# ESC.net
KiCad netlist of a schematic drawn in EAGLE
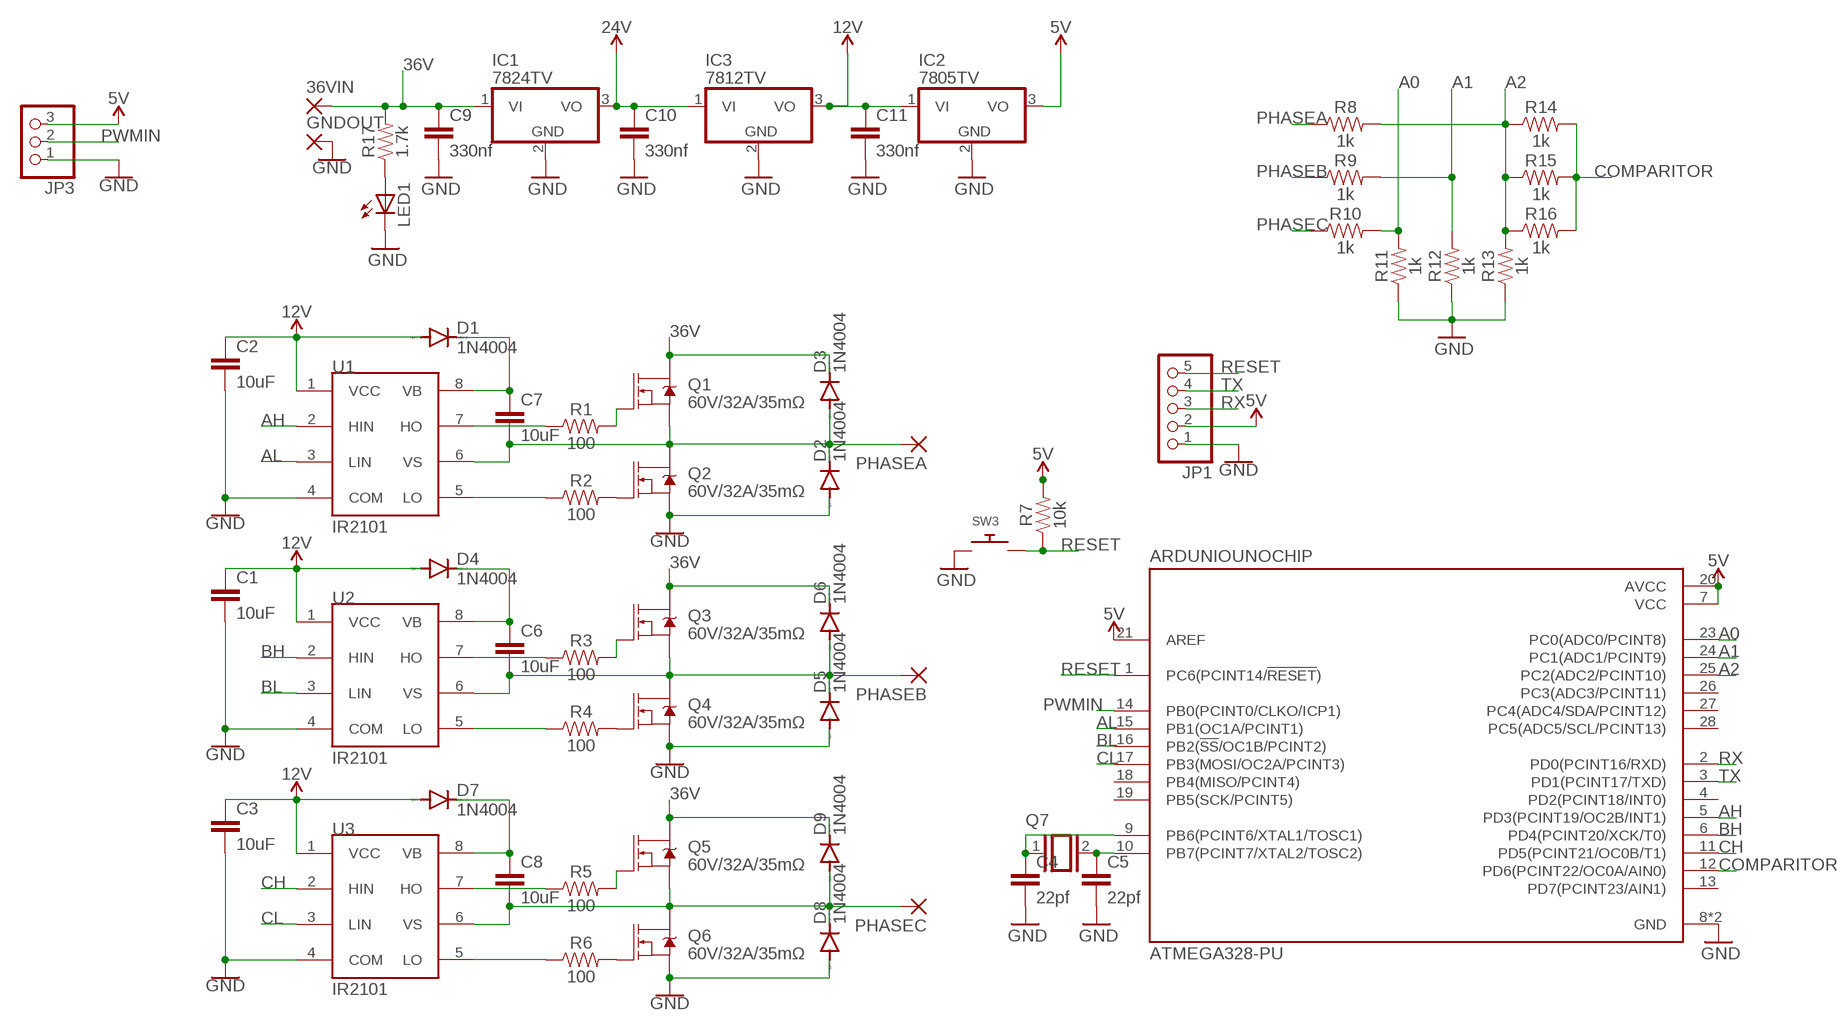
[diagram p0: schematic, sheet 1]

(export (version "E")
  (design (tool "Eeschema 10.0.6"))
  (components
    (comp (ref "36VIN")
      (value "2,15/1,0")
      (footprint "eagle-import:2,15_1,0")
      (libsource (lib "eagle-import") (part "2,15/1,0"))
    )
    (comp (ref "ARDUNIOUNOCHIP")
      (value "ATMEGA328-PU")
      (footprint "eagle-import:DIP787W46P254L3467H508Q28")
      (fields (field (name "MF") "Microchip Technology"))
      (libsource (lib "eagle-import") (part "ATMEGA328-PU"))
    )
    (comp (ref "C1")
      (value "10uF")
      (footprint "eagle-import:CAP-PTH-10MM")
      (libsource (lib "eagle-import") (part "10NF-PTH-10MM-10000V-1-%"))
    )
    (comp (ref "C2")
      (value "10uF")
      (footprint "eagle-import:CAP-PTH-10MM")
      (libsource (lib "eagle-import") (part "10NF-PTH-10MM-10000V-1-%"))
    )
    (comp (ref "C3")
      (value "10uF")
      (footprint "eagle-import:CAP-PTH-10MM")
      (libsource (lib "eagle-import") (part "10NF-PTH-10MM-10000V-1-%"))
    )
    (comp (ref "C4")
      (value "22pf")
      (footprint "eagle-import:CAP-PTH-10MM")
      (libsource (lib "eagle-import") (part "10NF-PTH-10MM-10000V-1-%"))
    )
    (comp (ref "C5")
      (value "22pf")
      (footprint "eagle-import:CAP-PTH-10MM")
      (libsource (lib "eagle-import") (part "10NF-PTH-10MM-10000V-1-%"))
    )
    (comp (ref "C6")
      (value "10uF")
      (footprint "eagle-import:CAP-PTH-10MM")
      (libsource (lib "eagle-import") (part "10NF-PTH-10MM-10000V-1-%"))
    )
    (comp (ref "C7")
      (value "10uF")
      (footprint "eagle-import:CAP-PTH-10MM")
      (libsource (lib "eagle-import") (part "10NF-PTH-10MM-10000V-1-%"))
    )
    (comp (ref "C8")
      (value "10uF")
      (footprint "eagle-import:CAP-PTH-10MM")
      (libsource (lib "eagle-import") (part "10NF-PTH-10MM-10000V-1-%"))
    )
    (comp (ref "C9")
      (value "330nf")
      (footprint "eagle-import:CAP-PTH-10MM")
      (libsource (lib "eagle-import") (part "10NF-PTH-10MM-10000V-1-%"))
    )
    (comp (ref "C10")
      (value "330nf")
      (footprint "eagle-import:CAP-PTH-10MM")
      (libsource (lib "eagle-import") (part "10NF-PTH-10MM-10000V-1-%"))
    )
    (comp (ref "C11")
      (value "330nf")
      (footprint "eagle-import:CAP-PTH-10MM")
      (libsource (lib "eagle-import") (part "10NF-PTH-10MM-10000V-1-%"))
    )
    (comp (ref "D1")
      (value "1N4004")
      (footprint "eagle-import:DO41-10")
      (libsource (lib "eagle-import") (part "1N4004"))
    )
    (comp (ref "D2")
      (value "1N4004")
      (footprint "eagle-import:DO41-10")
      (libsource (lib "eagle-import") (part "1N4004"))
    )
    (comp (ref "D3")
      (value "1N4004")
      (footprint "eagle-import:DO41-10")
      (libsource (lib "eagle-import") (part "1N4004"))
    )
    (comp (ref "D4")
      (value "1N4004")
      (footprint "eagle-import:DO41-10")
      (libsource (lib "eagle-import") (part "1N4004"))
    )
    (comp (ref "D5")
      (value "1N4004")
      (footprint "eagle-import:DO41-10")
      (libsource (lib "eagle-import") (part "1N4004"))
    )
    (comp (ref "D6")
      (value "1N4004")
      (footprint "eagle-import:DO41-10")
      (libsource (lib "eagle-import") (part "1N4004"))
    )
    (comp (ref "D7")
      (value "1N4004")
      (footprint "eagle-import:DO41-10")
      (libsource (lib "eagle-import") (part "1N4004"))
    )
    (comp (ref "D8")
      (value "1N4004")
      (footprint "eagle-import:DO41-10")
      (libsource (lib "eagle-import") (part "1N4004"))
    )
    (comp (ref "D9")
      (value "1N4004")
      (footprint "eagle-import:DO41-10")
      (libsource (lib "eagle-import") (part "1N4004"))
    )
    (comp (ref "GNDOUT")
      (value "2,15/1,0")
      (footprint "eagle-import:2,15_1,0")
      (libsource (lib "eagle-import") (part "2,15/1,0"))
    )
    (comp (ref "IC1")
      (value "7824TV")
      (footprint "eagle-import:TO220V")
      (libsource (lib "eagle-import") (part "78TV24"))
    )
    (comp (ref "IC2")
      (value "7805TV")
      (footprint "eagle-import:TO220V")
      (libsource (lib "eagle-import") (part "78TV05"))
    )
    (comp (ref "IC3")
      (value "7812TV")
      (footprint "eagle-import:TO220V")
      (libsource (lib "eagle-import") (part "78TV05"))
    )
    (comp (ref "JP1")
      (value "PINHD-1X5")
      (footprint "eagle-import:1X05")
      (libsource (lib "eagle-import") (part "PINHD-1X5"))
    )
    (comp (ref "JP3")
      (value "PINHD-1X3")
      (footprint "eagle-import:1X03")
      (libsource (lib "eagle-import") (part "PINHD-1X3"))
    )
    (comp (ref "LED1")
      (value "LED5MM")
      (footprint "eagle-import:LED5MM")
      (libsource (lib "eagle-import") (part "LED5MM"))
    )
    (comp (ref "PHASEA")
      (value "2,15/1,0")
      (footprint "eagle-import:2,15_1,0")
      (libsource (lib "eagle-import") (part "2,15/1,0"))
    )
    (comp (ref "PHASEB")
      (value "2,15/1,0")
      (footprint "eagle-import:2,15_1,0")
      (libsource (lib "eagle-import") (part "2,15/1,0"))
    )
    (comp (ref "PHASEC")
      (value "2,15/1,0")
      (footprint "eagle-import:2,15_1,0")
      (libsource (lib "eagle-import") (part "2,15/1,0"))
    )
    (comp (ref "Q1")
      (value "60V/32A/35mΩ")
      (footprint "eagle-import:TO220V")
      (libsource (lib "eagle-import") (part "MOSFET-NCH-FQP30N06L"))
    )
    (comp (ref "Q2")
      (value "60V/32A/35mΩ")
      (footprint "eagle-import:TO220V")
      (libsource (lib "eagle-import") (part "MOSFET-NCH-FQP30N06L"))
    )
    (comp (ref "Q3")
      (value "60V/32A/35mΩ")
      (footprint "eagle-import:TO220V")
      (libsource (lib "eagle-import") (part "MOSFET-NCH-FQP30N06L"))
    )
    (comp (ref "Q4")
      (value "60V/32A/35mΩ")
      (footprint "eagle-import:TO220V")
      (libsource (lib "eagle-import") (part "MOSFET-NCH-FQP30N06L"))
    )
    (comp (ref "Q5")
      (value "60V/32A/35mΩ")
      (footprint "eagle-import:TO220V")
      (libsource (lib "eagle-import") (part "MOSFET-NCH-FQP30N06L"))
    )
    (comp (ref "Q6")
      (value "60V/32A/35mΩ")
      (footprint "eagle-import:TO220V")
      (libsource (lib "eagle-import") (part "MOSFET-NCH-FQP30N06L"))
    )
    (comp (ref "Q7")
      (value "XTAL/S")
      (footprint "eagle-import:QS")
      (libsource (lib "eagle-import") (part "XTAL/S"))
    )
    (comp (ref "R1")
      (value "100")
      (footprint "eagle-import:AXIAL-0.3")
      (libsource (lib "eagle-import") (part "1MOHM-HORIZ-1/4W-5%"))
    )
    (comp (ref "R2")
      (value "100")
      (footprint "eagle-import:AXIAL-0.3")
      (libsource (lib "eagle-import") (part "1MOHM-HORIZ-1/4W-5%"))
    )
    (comp (ref "R3")
      (value "100")
      (footprint "eagle-import:AXIAL-0.3")
      (libsource (lib "eagle-import") (part "1MOHM-HORIZ-1/4W-5%"))
    )
    (comp (ref "R4")
      (value "100")
      (footprint "eagle-import:AXIAL-0.3")
      (libsource (lib "eagle-import") (part "1MOHM-HORIZ-1/4W-5%"))
    )
    (comp (ref "R5")
      (value "100")
      (footprint "eagle-import:AXIAL-0.3")
      (libsource (lib "eagle-import") (part "1MOHM-HORIZ-1/4W-5%"))
    )
    (comp (ref "R6")
      (value "100")
      (footprint "eagle-import:AXIAL-0.3")
      (libsource (lib "eagle-import") (part "1MOHM-HORIZ-1/4W-5%"))
    )
    (comp (ref "R7")
      (value "10k")
      (footprint "eagle-import:AXIAL-0.3")
      (libsource (lib "eagle-import") (part "10KOHM-HORIZ-1/4W-1%"))
    )
    (comp (ref "R8")
      (value "1k")
      (footprint "eagle-import:AXIAL-0.3")
      (libsource (lib "eagle-import") (part "1KOHM-HORIZ-1/4W-1%"))
    )
    (comp (ref "R9")
      (value "1k")
      (footprint "eagle-import:AXIAL-0.3")
      (libsource (lib "eagle-import") (part "1KOHM-HORIZ-1/4W-1%"))
    )
    (comp (ref "R10")
      (value "1k")
      (footprint "eagle-import:AXIAL-0.3")
      (libsource (lib "eagle-import") (part "1KOHM-HORIZ-1/4W-1%"))
    )
    (comp (ref "R11")
      (value "1k")
      (footprint "eagle-import:AXIAL-0.3")
      (libsource (lib "eagle-import") (part "1KOHM-HORIZ-1/4W-1%"))
    )
    (comp (ref "R12")
      (value "1k")
      (footprint "eagle-import:AXIAL-0.3")
      (libsource (lib "eagle-import") (part "1KOHM-HORIZ-1/4W-1%"))
    )
    (comp (ref "R13")
      (value "1k")
      (footprint "eagle-import:AXIAL-0.3")
      (libsource (lib "eagle-import") (part "1KOHM-HORIZ-1/4W-1%"))
    )
    (comp (ref "R14")
      (value "1k")
      (footprint "eagle-import:AXIAL-0.3")
      (libsource (lib "eagle-import") (part "1KOHM-HORIZ-1/4W-1%"))
    )
    (comp (ref "R15")
      (value "1k")
      (footprint "eagle-import:AXIAL-0.3")
      (libsource (lib "eagle-import") (part "1KOHM-HORIZ-1/4W-1%"))
    )
    (comp (ref "R16")
      (value "1k")
      (footprint "eagle-import:AXIAL-0.3")
      (libsource (lib "eagle-import") (part "1KOHM-HORIZ-1/4W-1%"))
    )
    (comp (ref "R17")
      (value "1.7k")
      (footprint "eagle-import:AXIAL-0.3")
      (libsource (lib "eagle-import") (part "1KOHM-HORIZ-1/4W-1%"))
    )
    (comp (ref "SW3")
      (value "SWITCH_PUSHBUTTONEVQ-PE")
      (footprint "eagle-import:TACT_PANA-EVQ")
      (libsource (lib "eagle-import") (part "SWITCH_PUSHBUTTONEVQ-PE"))
    )
    (comp (ref "U1")
      (value "IR2101")
      (footprint "eagle-import:DIL08")
      (fields (field (name "MF") "Infineon"))
      (libsource (lib "eagle-import") (part "IR2101"))
    )
    (comp (ref "U2")
      (value "IR2101")
      (footprint "eagle-import:DIL08")
      (fields (field (name "MF") "Infineon"))
      (libsource (lib "eagle-import") (part "IR2101"))
    )
    (comp (ref "U3")
      (value "IR2101")
      (footprint "eagle-import:DIL08")
      (fields (field (name "MF") "Infineon"))
      (libsource (lib "eagle-import") (part "IR2101"))
    )
  )
  (nets
    (net (code "1") (name "5V") (class "Default")
      (node (ref "ARDUNIOUNOCHIP") (pin "20") (pinfunction "AVCC_20") (pintype "power_in"))
      (node (ref "ARDUNIOUNOCHIP") (pin "21") (pinfunction "AREF_21") (pintype "input"))
      (node (ref "ARDUNIOUNOCHIP") (pin "7") (pinfunction "VCC_7") (pintype "power_in"))
      (node (ref "IC2") (pin "3") (pinfunction "VO_3") (pintype "passive"))
      (node (ref "JP1") (pin "2") (pinfunction "2_2") (pintype "passive"))
      (node (ref "JP3") (pin "3") (pinfunction "3_3") (pintype "passive"))
      (node (ref "R7") (pin "P$2") (pinfunction "2_P$2") (pintype "passive"))
    )
    (net (code "2") (name "24V") (class "Default")
      (node (ref "C10") (pin "1") (pinfunction "1_1") (pintype "passive"))
      (node (ref "IC1") (pin "3") (pinfunction "VO_3") (pintype "passive"))
      (node (ref "IC3") (pin "1") (pinfunction "VI_1") (pintype "input"))
    )
    (net (code "3") (name "36V") (class "Default")
      (node (ref "36VIN") (pin "1") (pinfunction "P_1") (pintype "passive"))
      (node (ref "C9") (pin "1") (pinfunction "1_1") (pintype "passive"))
      (node (ref "D3") (pin "C") (pinfunction "C_C") (pintype "passive"))
      (node (ref "D6") (pin "C") (pinfunction "C_C") (pintype "passive"))
      (node (ref "D9") (pin "C") (pinfunction "C_C") (pintype "passive"))
      (node (ref "IC1") (pin "1") (pinfunction "VI_1") (pintype "input"))
      (node (ref "Q1") (pin "2") (pinfunction "D_2") (pintype "bidirectional"))
      (node (ref "Q3") (pin "2") (pinfunction "D_2") (pintype "bidirectional"))
      (node (ref "Q5") (pin "2") (pinfunction "D_2") (pintype "bidirectional"))
      (node (ref "R17") (pin "P$2") (pinfunction "2_P$2") (pintype "passive"))
    )
    (net (code "4") (name "A0") (class "Default")
      (node (ref "ARDUNIOUNOCHIP") (pin "23") (pinfunction "PC0(ADC0/PCINT8)_23") (pintype "bidirectional"))
      (node (ref "R10") (pin "P$2") (pinfunction "2_P$2") (pintype "passive"))
      (node (ref "R11") (pin "P$2") (pinfunction "2_P$2") (pintype "passive"))
    )
    (net (code "5") (name "A1") (class "Default")
      (node (ref "ARDUNIOUNOCHIP") (pin "24") (pinfunction "PC1(ADC1/PCINT9)_24") (pintype "bidirectional"))
      (node (ref "R12") (pin "P$2") (pinfunction "2_P$2") (pintype "passive"))
      (node (ref "R9") (pin "P$2") (pinfunction "2_P$2") (pintype "passive"))
    )
    (net (code "6") (name "A2") (class "Default")
      (node (ref "ARDUNIOUNOCHIP") (pin "25") (pinfunction "PC2(ADC2/PCINT10)_25") (pintype "bidirectional"))
      (node (ref "R13") (pin "P$2") (pinfunction "2_P$2") (pintype "passive"))
      (node (ref "R14") (pin "P$1") (pinfunction "1_P$1") (pintype "passive"))
      (node (ref "R15") (pin "P$1") (pinfunction "1_P$1") (pintype "passive"))
      (node (ref "R16") (pin "P$1") (pinfunction "1_P$1") (pintype "passive"))
      (node (ref "R8") (pin "P$2") (pinfunction "2_P$2") (pintype "passive"))
    )
    (net (code "7") (name "AH") (class "Default")
      (node (ref "ARDUNIOUNOCHIP") (pin "5") (pinfunction "PD3(PCINT19/OC2B/INT1)_5") (pintype "bidirectional"))
      (node (ref "U1") (pin "2") (pinfunction "HIN_2") (pintype "input"))
    )
    (net (code "8") (name "AL") (class "Default")
      (node (ref "ARDUNIOUNOCHIP") (pin "15") (pinfunction "PB1(OC1A/PCINT1)_15") (pintype "bidirectional"))
      (node (ref "U1") (pin "3") (pinfunction "LIN_3") (pintype "input"))
    )
    (net (code "9") (name "BH") (class "Default")
      (node (ref "ARDUNIOUNOCHIP") (pin "6") (pinfunction "PD4(PCINT20/XCK/T0)_6") (pintype "bidirectional"))
      (node (ref "U2") (pin "2") (pinfunction "HIN_2") (pintype "input"))
    )
    (net (code "10") (name "BL") (class "Default")
      (node (ref "ARDUNIOUNOCHIP") (pin "16") (pinfunction "PB2(~{SS}/OC1B/PCINT2)_16") (pintype "bidirectional"))
      (node (ref "U2") (pin "3") (pinfunction "LIN_3") (pintype "input"))
    )
    (net (code "11") (name "CH") (class "Default")
      (node (ref "ARDUNIOUNOCHIP") (pin "11") (pinfunction "PD5(PCINT21/OC0B/T1)_11") (pintype "bidirectional"))
      (node (ref "U3") (pin "2") (pinfunction "HIN_2") (pintype "input"))
    )
    (net (code "12") (name "CL") (class "Default")
      (node (ref "ARDUNIOUNOCHIP") (pin "17") (pinfunction "PB3(MOSI/OC2A/PCINT3)_17") (pintype "bidirectional"))
      (node (ref "U3") (pin "3") (pinfunction "LIN_3") (pintype "input"))
    )
    (net (code "13") (name "COMPARITOR") (class "Default")
      (node (ref "ARDUNIOUNOCHIP") (pin "12") (pinfunction "PD6(PCINT22/OC0A/AIN0)_12") (pintype "bidirectional"))
      (node (ref "R14") (pin "P$2") (pinfunction "2_P$2") (pintype "passive"))
      (node (ref "R15") (pin "P$2") (pinfunction "2_P$2") (pintype "passive"))
      (node (ref "R16") (pin "P$2") (pinfunction "2_P$2") (pintype "passive"))
    )
    (net (code "14") (name "GND") (class "Default")
      (node (ref "ARDUNIOUNOCHIP") (pin "22") (pinfunction "GND_22") (pintype "power_in"))
      (node (ref "ARDUNIOUNOCHIP") (pin "8") (pinfunction "GND_8") (pintype "power_in"))
      (node (ref "C1") (pin "2") (pinfunction "2_2") (pintype "passive"))
      (node (ref "C10") (pin "2") (pinfunction "2_2") (pintype "passive"))
      (node (ref "C11") (pin "2") (pinfunction "2_2") (pintype "passive"))
      (node (ref "C2") (pin "2") (pinfunction "2_2") (pintype "passive"))
      (node (ref "C3") (pin "2") (pinfunction "2_2") (pintype "passive"))
      (node (ref "C4") (pin "2") (pinfunction "2_2") (pintype "passive"))
      (node (ref "C5") (pin "2") (pinfunction "2_2") (pintype "passive"))
      (node (ref "C9") (pin "2") (pinfunction "2_2") (pintype "passive"))
      (node (ref "D2") (pin "A") (pinfunction "A_A") (pintype "passive"))
      (node (ref "D5") (pin "A") (pinfunction "A_A") (pintype "passive"))
      (node (ref "D8") (pin "A") (pinfunction "A_A") (pintype "passive"))
      (node (ref "GNDOUT") (pin "1") (pinfunction "P_1") (pintype "passive"))
      (node (ref "IC1") (pin "2") (pinfunction "GND_2") (pintype "passive"))
      (node (ref "IC2") (pin "2") (pinfunction "GND_2") (pintype "passive"))
      (node (ref "IC3") (pin "2") (pinfunction "GND_2") (pintype "passive"))
      (node (ref "JP1") (pin "1") (pinfunction "1_1") (pintype "passive"))
      (node (ref "JP3") (pin "1") (pinfunction "1_1") (pintype "passive"))
      (node (ref "LED1") (pin "K") (pinfunction "C_K") (pintype "passive"))
      (node (ref "Q2") (pin "3") (pinfunction "S_3") (pintype "bidirectional"))
      (node (ref "Q4") (pin "3") (pinfunction "S_3") (pintype "bidirectional"))
      (node (ref "Q6") (pin "3") (pinfunction "S_3") (pintype "bidirectional"))
      (node (ref "R11") (pin "P$1") (pinfunction "1_P$1") (pintype "passive"))
      (node (ref "R12") (pin "P$1") (pinfunction "1_P$1") (pintype "passive"))
      (node (ref "R13") (pin "P$1") (pinfunction "1_P$1") (pintype "passive"))
      (node (ref "SW3") (pin "P$1") (pinfunction "P$1_P$1") (pintype "passive"))
      (node (ref "U1") (pin "4") (pinfunction "COM_4") (pintype "power_in"))
      (node (ref "U2") (pin "4") (pinfunction "COM_4") (pintype "power_in"))
      (node (ref "U3") (pin "4") (pinfunction "COM_4") (pintype "power_in"))
    )
    (net (code "15") (name "Net-(ARDUNIOUNOCHIP-PB6(PCINT6{slash}XTAL1{slash}TOSC1))") (class "Default")
      (node (ref "ARDUNIOUNOCHIP") (pin "9") (pinfunction "PB6(PCINT6/XTAL1/TOSC1)_9") (pintype "bidirectional"))
      (node (ref "C4") (pin "1") (pinfunction "1_1") (pintype "passive"))
      (node (ref "Q7") (pin "1") (pinfunction "1_1") (pintype "passive"))
    )
    (net (code "16") (name "Net-(ARDUNIOUNOCHIP-PB7(PCINT7{slash}XTAL2{slash}TOSC2))") (class "Default")
      (node (ref "ARDUNIOUNOCHIP") (pin "10") (pinfunction "PB7(PCINT7/XTAL2/TOSC2)_10") (pintype "bidirectional"))
      (node (ref "C5") (pin "1") (pinfunction "1_1") (pintype "passive"))
      (node (ref "Q7") (pin "2") (pinfunction "2_2") (pintype "passive"))
    )
    (net (code "17") (name "Net-(Q1-G)") (class "Default")
      (node (ref "Q1") (pin "1") (pinfunction "G_1") (pintype "bidirectional"))
      (node (ref "R1") (pin "P$2") (pinfunction "2_P$2") (pintype "passive"))
    )
    (net (code "18") (name "Net-(Q2-G)") (class "Default")
      (node (ref "Q2") (pin "1") (pinfunction "G_1") (pintype "bidirectional"))
      (node (ref "R2") (pin "P$2") (pinfunction "2_P$2") (pintype "passive"))
    )
    (net (code "19") (name "Net-(Q3-G)") (class "Default")
      (node (ref "Q3") (pin "1") (pinfunction "G_1") (pintype "bidirectional"))
      (node (ref "R3") (pin "P$2") (pinfunction "2_P$2") (pintype "passive"))
    )
    (net (code "20") (name "Net-(Q4-G)") (class "Default")
      (node (ref "Q4") (pin "1") (pinfunction "G_1") (pintype "bidirectional"))
      (node (ref "R4") (pin "P$2") (pinfunction "2_P$2") (pintype "passive"))
    )
    (net (code "21") (name "Net-(Q5-G)") (class "Default")
      (node (ref "Q5") (pin "1") (pinfunction "G_1") (pintype "bidirectional"))
      (node (ref "R5") (pin "P$2") (pinfunction "2_P$2") (pintype "passive"))
    )
    (net (code "22") (name "Net-(Q6-G)") (class "Default")
      (node (ref "Q6") (pin "1") (pinfunction "G_1") (pintype "bidirectional"))
      (node (ref "R6") (pin "P$2") (pinfunction "2_P$2") (pintype "passive"))
    )
    (net (code "23") (name "Net-(R1-1)") (class "Default")
      (node (ref "R1") (pin "P$1") (pinfunction "1_P$1") (pintype "passive"))
      (node (ref "U1") (pin "7") (pinfunction "HO_7") (pintype "output"))
    )
    (net (code "24") (name "Net-(R2-1)") (class "Default")
      (node (ref "R2") (pin "P$1") (pinfunction "1_P$1") (pintype "passive"))
      (node (ref "U1") (pin "5") (pinfunction "LO_5") (pintype "output"))
    )
    (net (code "25") (name "Net-(R3-1)") (class "Default")
      (node (ref "R3") (pin "P$1") (pinfunction "1_P$1") (pintype "passive"))
      (node (ref "U2") (pin "7") (pinfunction "HO_7") (pintype "output"))
    )
    (net (code "26") (name "Net-(R4-1)") (class "Default")
      (node (ref "R4") (pin "P$1") (pinfunction "1_P$1") (pintype "passive"))
      (node (ref "U2") (pin "5") (pinfunction "LO_5") (pintype "output"))
    )
    (net (code "27") (name "Net-(R5-1)") (class "Default")
      (node (ref "R5") (pin "P$1") (pinfunction "1_P$1") (pintype "passive"))
      (node (ref "U3") (pin "7") (pinfunction "HO_7") (pintype "output"))
    )
    (net (code "28") (name "Net-(R6-1)") (class "Default")
      (node (ref "R6") (pin "P$1") (pinfunction "1_P$1") (pintype "passive"))
      (node (ref "U3") (pin "5") (pinfunction "LO_5") (pintype "output"))
    )
    (net (code "29") (name "Net-(R17-1)") (class "Default")
      (node (ref "LED1") (pin "A") (pinfunction "A_A") (pintype "passive"))
      (node (ref "R17") (pin "P$1") (pinfunction "1_P$1") (pintype "passive"))
    )
    (net (code "30") (name "PHASEA") (class "Default")
      (node (ref "C7") (pin "2") (pinfunction "2_2") (pintype "passive"))
      (node (ref "D2") (pin "C") (pinfunction "C_C") (pintype "passive"))
      (node (ref "D3") (pin "A") (pinfunction "A_A") (pintype "passive"))
      (node (ref "PHASEA") (pin "1") (pinfunction "P_1") (pintype "passive"))
      (node (ref "Q1") (pin "3") (pinfunction "S_3") (pintype "bidirectional"))
      (node (ref "Q2") (pin "2") (pinfunction "D_2") (pintype "bidirectional"))
      (node (ref "R8") (pin "P$1") (pinfunction "1_P$1") (pintype "passive"))
      (node (ref "U1") (pin "6") (pinfunction "VS_6") (pintype "output"))
    )
    (net (code "31") (name "PHASEB") (class "Default")
      (node (ref "C6") (pin "2") (pinfunction "2_2") (pintype "passive"))
      (node (ref "D5") (pin "C") (pinfunction "C_C") (pintype "passive"))
      (node (ref "D6") (pin "A") (pinfunction "A_A") (pintype "passive"))
      (node (ref "PHASEB") (pin "1") (pinfunction "P_1") (pintype "passive"))
      (node (ref "Q3") (pin "3") (pinfunction "S_3") (pintype "bidirectional"))
      (node (ref "Q4") (pin "2") (pinfunction "D_2") (pintype "bidirectional"))
      (node (ref "R9") (pin "P$1") (pinfunction "1_P$1") (pintype "passive"))
      (node (ref "U2") (pin "6") (pinfunction "VS_6") (pintype "output"))
    )
    (net (code "32") (name "PHASEC") (class "Default")
      (node (ref "C8") (pin "2") (pinfunction "2_2") (pintype "passive"))
      (node (ref "D8") (pin "C") (pinfunction "C_C") (pintype "passive"))
      (node (ref "D9") (pin "A") (pinfunction "A_A") (pintype "passive"))
      (node (ref "PHASEC") (pin "1") (pinfunction "P_1") (pintype "passive"))
      (node (ref "Q5") (pin "3") (pinfunction "S_3") (pintype "bidirectional"))
      (node (ref "Q6") (pin "2") (pinfunction "D_2") (pintype "bidirectional"))
      (node (ref "R10") (pin "P$1") (pinfunction "1_P$1") (pintype "passive"))
      (node (ref "U3") (pin "6") (pinfunction "VS_6") (pintype "output"))
    )
    (net (code "33") (name "PWMIN") (class "Default")
      (node (ref "ARDUNIOUNOCHIP") (pin "14") (pinfunction "PB0(PCINT0/CLKO/ICP1)_14") (pintype "bidirectional"))
      (node (ref "JP3") (pin "2") (pinfunction "2_2") (pintype "passive"))
    )
    (net (code "34") (name "RESET") (class "Default")
      (node (ref "ARDUNIOUNOCHIP") (pin "1") (pinfunction "PC6(PCINT14/~{RESET})_1") (pintype "bidirectional"))
      (node (ref "JP1") (pin "5") (pinfunction "5_5") (pintype "passive"))
      (node (ref "R7") (pin "P$1") (pinfunction "1_P$1") (pintype "passive"))
      (node (ref "SW3") (pin "P$2") (pinfunction "P$2_P$2") (pintype "passive"))
    )
    (net (code "35") (name "RX") (class "Default")
      (node (ref "ARDUNIOUNOCHIP") (pin "2") (pinfunction "PD0(PCINT16/RXD)_2") (pintype "bidirectional"))
      (node (ref "JP1") (pin "3") (pinfunction "3_3") (pintype "passive"))
    )
    (net (code "36") (name "TX") (class "Default")
      (node (ref "ARDUNIOUNOCHIP") (pin "3") (pinfunction "PD1(PCINT17/TXD)_3") (pintype "bidirectional"))
      (node (ref "JP1") (pin "4") (pinfunction "4_4") (pintype "passive"))
    )
    (net (code "37") (name "VB") (class "Default")
      (node (ref "C6") (pin "1") (pinfunction "1_1") (pintype "passive"))
      (node (ref "C7") (pin "1") (pinfunction "1_1") (pintype "passive"))
      (node (ref "C8") (pin "1") (pinfunction "1_1") (pintype "passive"))
      (node (ref "D1") (pin "C") (pinfunction "C_C") (pintype "passive"))
      (node (ref "D4") (pin "C") (pinfunction "C_C") (pintype "passive"))
      (node (ref "D7") (pin "C") (pinfunction "C_C") (pintype "passive"))
      (node (ref "U1") (pin "8") (pinfunction "VB_8") (pintype "power_in"))
      (node (ref "U2") (pin "8") (pinfunction "VB_8") (pintype "power_in"))
      (node (ref "U3") (pin "8") (pinfunction "VB_8") (pintype "power_in"))
    )
    (net (code "38") (name "VCC") (class "Default")
      (node (ref "C1") (pin "1") (pinfunction "1_1") (pintype "passive"))
      (node (ref "C11") (pin "1") (pinfunction "1_1") (pintype "passive"))
      (node (ref "C2") (pin "1") (pinfunction "1_1") (pintype "passive"))
      (node (ref "C3") (pin "1") (pinfunction "1_1") (pintype "passive"))
      (node (ref "D1") (pin "A") (pinfunction "A_A") (pintype "passive"))
      (node (ref "D4") (pin "A") (pinfunction "A_A") (pintype "passive"))
      (node (ref "D7") (pin "A") (pinfunction "A_A") (pintype "passive"))
      (node (ref "IC2") (pin "1") (pinfunction "VI_1") (pintype "input"))
      (node (ref "IC3") (pin "3") (pinfunction "VO_3") (pintype "passive"))
      (node (ref "U1") (pin "1") (pinfunction "VCC_1") (pintype "power_in"))
      (node (ref "U2") (pin "1") (pinfunction "VCC_1") (pintype "power_in"))
      (node (ref "U3") (pin "1") (pinfunction "VCC_1") (pintype "power_in"))
    )
    (net (code "39") (name "unconnected-(ARDUNIOUNOCHIP-PB4(MISO{slash}PCINT4)-Pad18)") (class "Default")
      (node (ref "ARDUNIOUNOCHIP") (pin "18") (pinfunction "PB4(MISO/PCINT4)_18") (pintype "bidirectional"))
    )
    (net (code "40") (name "unconnected-(ARDUNIOUNOCHIP-PB5(SCK{slash}PCINT5)-Pad19)") (class "Default")
      (node (ref "ARDUNIOUNOCHIP") (pin "19") (pinfunction "PB5(SCK/PCINT5)_19") (pintype "bidirectional"))
    )
    (net (code "41") (name "unconnected-(ARDUNIOUNOCHIP-PC3(ADC3{slash}PCINT11)-Pad26)") (class "Default")
      (node (ref "ARDUNIOUNOCHIP") (pin "26") (pinfunction "PC3(ADC3/PCINT11)_26") (pintype "bidirectional"))
    )
    (net (code "42") (name "unconnected-(ARDUNIOUNOCHIP-PC4(ADC4{slash}SDA{slash}PCINT12)-Pad27)") (class "Default")
      (node (ref "ARDUNIOUNOCHIP") (pin "27") (pinfunction "PC4(ADC4/SDA/PCINT12)_27") (pintype "bidirectional"))
    )
    (net (code "43") (name "unconnected-(ARDUNIOUNOCHIP-PC5(ADC5{slash}SCL{slash}PCINT13)-Pad28)") (class "Default")
      (node (ref "ARDUNIOUNOCHIP") (pin "28") (pinfunction "PC5(ADC5/SCL/PCINT13)_28") (pintype "bidirectional"))
    )
    (net (code "44") (name "unconnected-(ARDUNIOUNOCHIP-PD2(PCINT18{slash}INT0)-Pad4)") (class "Default")
      (node (ref "ARDUNIOUNOCHIP") (pin "4") (pinfunction "PD2(PCINT18/INT0)_4") (pintype "bidirectional"))
    )
    (net (code "45") (name "unconnected-(ARDUNIOUNOCHIP-PD7(PCINT23{slash}AIN1)-Pad13)") (class "Default")
      (node (ref "ARDUNIOUNOCHIP") (pin "13") (pinfunction "PD7(PCINT23/AIN1)_13") (pintype "bidirectional"))
    )
  )
)
